# WS2812B-compact.net
KiCad netlist of a schematic drawn in EAGLE
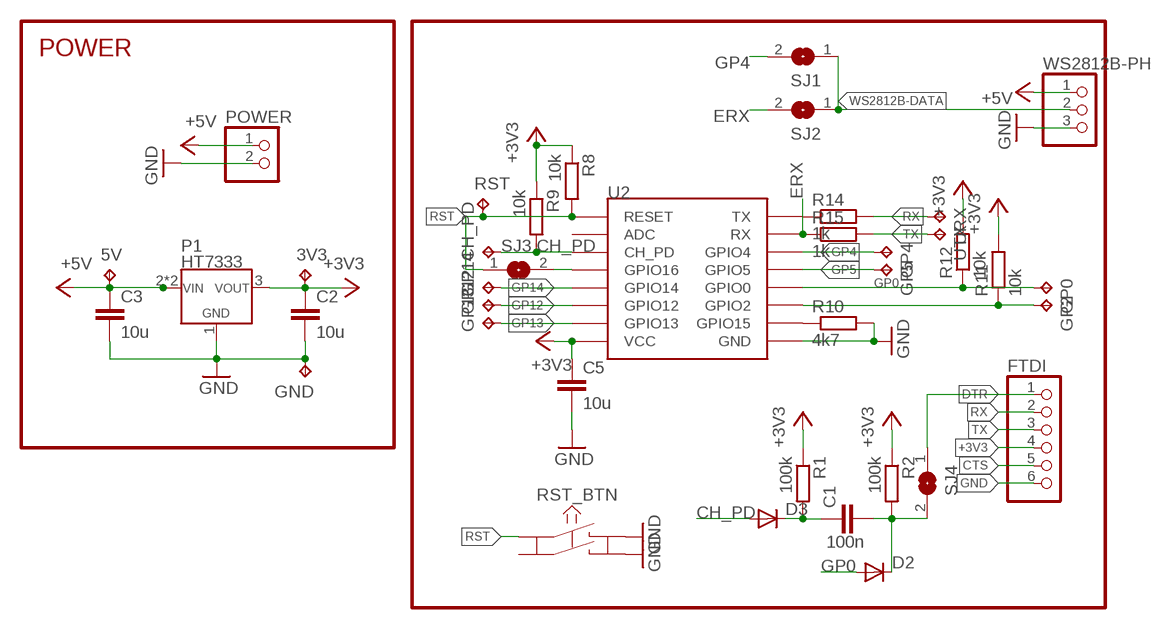
[diagram p0: schematic, sheet 1]

(export (version "E")
  (design (tool "Eeschema 10.0.6"))
  (components
    (comp (ref "3V3")
      (value "TPB2,54")
      (footprint "eagle-import:B2,54")
      (libsource (lib "eagle-import") (part "TPB2,54"))
    )
    (comp (ref "5V")
      (value "TPB2,54")
      (footprint "eagle-import:B2,54")
      (libsource (lib "eagle-import") (part "TPB2,54"))
    )
    (comp (ref "C1")
      (value "100n")
      (footprint "eagle-import:C1206")
      (libsource (lib "eagle-import") (part "C-EUC1206"))
    )
    (comp (ref "C2")
      (value "10u")
      (footprint "eagle-import:C1206")
      (libsource (lib "eagle-import") (part "C-EUC1206"))
    )
    (comp (ref "C3")
      (value "10u")
      (footprint "eagle-import:C1206")
      (libsource (lib "eagle-import") (part "C-EUC1206"))
    )
    (comp (ref "C5")
      (value "10u")
      (footprint "eagle-import:C1206")
      (libsource (lib "eagle-import") (part "C-EUC1206"))
    )
    (comp (ref "CH_PD")
      (value "TPB1,27")
      (footprint "eagle-import:B1,27")
      (libsource (lib "eagle-import") (part "TPB1,27"))
    )
    (comp (ref "D2")
      (value "DIODE-MINIMELF")
      (footprint "eagle-import:MINIMELF")
      (libsource (lib "eagle-import") (part "DIODE-MINIMELF"))
    )
    (comp (ref "D3")
      (value "DIODE-MINIMELF")
      (footprint "eagle-import:MINIMELF")
      (libsource (lib "eagle-import") (part "DIODE-MINIMELF"))
    )
    (comp (ref "FTDI")
      (value "PINHD-1X06_2.54-S")
      (footprint "eagle-import:1X06-S")
      (libsource (lib "eagle-import") (part "PINHD-1X06_2.54-S"))
    )
    (comp (ref "GND")
      (value "TPB2,54")
      (footprint "eagle-import:B2,54")
      (libsource (lib "eagle-import") (part "TPB2,54"))
    )
    (comp (ref "GP0")
      (value "TPB1,27")
      (footprint "eagle-import:B1,27")
      (libsource (lib "eagle-import") (part "TPB1,27"))
    )
    (comp (ref "GP2")
      (value "TPB1,27")
      (footprint "eagle-import:B1,27")
      (libsource (lib "eagle-import") (part "TPB1,27"))
    )
    (comp (ref "GP4")
      (value "TPB1,27")
      (footprint "eagle-import:B1,27")
      (libsource (lib "eagle-import") (part "TPB1,27"))
    )
    (comp (ref "GP5")
      (value "TPB1,27")
      (footprint "eagle-import:B1,27")
      (libsource (lib "eagle-import") (part "TPB1,27"))
    )
    (comp (ref "GP12")
      (value "TPB1,27")
      (footprint "eagle-import:B1,27")
      (libsource (lib "eagle-import") (part "TPB1,27"))
    )
    (comp (ref "GP13")
      (value "TPB1,27")
      (footprint "eagle-import:B1,27")
      (libsource (lib "eagle-import") (part "TPB1,27"))
    )
    (comp (ref "GP14")
      (value "TPB1,27")
      (footprint "eagle-import:B1,27")
      (libsource (lib "eagle-import") (part "TPB1,27"))
    )
    (comp (ref "P1")
      (value "HT7333")
      (footprint "eagle-import:SOT223")
      (libsource (lib "eagle-import") (part "HT7333"))
    )
    (comp (ref "POWER")
      (value "PINHD-1X2")
      (footprint "eagle-import:1X02")
      (libsource (lib "eagle-import") (part "PINHD-1X2"))
    )
    (comp (ref "R1")
      (value "100k")
      (footprint "eagle-import:R0805")
      (libsource (lib "eagle-import") (part "R-EU_R0805"))
    )
    (comp (ref "R2")
      (value "100k")
      (footprint "eagle-import:R0805")
      (libsource (lib "eagle-import") (part "R-EU_R0805"))
    )
    (comp (ref "R8")
      (value "10k")
      (footprint "eagle-import:R0805")
      (libsource (lib "eagle-import") (part "R-EU_R0805"))
    )
    (comp (ref "R9")
      (value "10k")
      (footprint "eagle-import:R0805")
      (libsource (lib "eagle-import") (part "R-EU_R0805"))
    )
    (comp (ref "R10")
      (value "4k7")
      (footprint "eagle-import:R0805")
      (libsource (lib "eagle-import") (part "R-EU_R0805"))
    )
    (comp (ref "R11")
      (value "10k")
      (footprint "eagle-import:R0805")
      (libsource (lib "eagle-import") (part "R-EU_R0805"))
    )
    (comp (ref "R12")
      (value "10k")
      (footprint "eagle-import:R0805")
      (libsource (lib "eagle-import") (part "R-EU_R0805"))
    )
    (comp (ref "R14")
      (value "1k")
      (footprint "eagle-import:R0805")
      (libsource (lib "eagle-import") (part "R-EU_R0805"))
    )
    (comp (ref "R15")
      (value "1k")
      (footprint "eagle-import:R0805")
      (libsource (lib "eagle-import") (part "R-EU_R0805"))
    )
    (comp (ref "RST")
      (value "TPB1,27")
      (footprint "eagle-import:B1,27")
      (libsource (lib "eagle-import") (part "TPB1,27"))
    )
    (comp (ref "RST_BTN")
      (value "KSM611A")
      (footprint "eagle-import:KSM611A")
      (libsource (lib "eagle-import") (part "KSM611A"))
    )
    (comp (ref "SJ1") (value "SJ") (footprint "eagle-import:SJ") (libsource (lib "eagle-import") (part "SJ")))
    (comp (ref "SJ2") (value "SJ") (footprint "eagle-import:SJ") (libsource (lib "eagle-import") (part "SJ")))
    (comp (ref "SJ3") (value "SJ") (footprint "eagle-import:SJ") (libsource (lib "eagle-import") (part "SJ")))
    (comp (ref "SJ4") (value "SJ") (footprint "eagle-import:SJ") (libsource (lib "eagle-import") (part "SJ")))
    (comp (ref "U2")
      (value "ESP12SMD")
      (footprint "eagle-import:ESP12-SMD")
      (libsource (lib "eagle-import") (part "ESP12SMD"))
    )
    (comp (ref "URX")
      (value "TPB1,27")
      (footprint "eagle-import:B1,27")
      (libsource (lib "eagle-import") (part "TPB1,27"))
    )
    (comp (ref "UTX")
      (value "TPB1,27")
      (footprint "eagle-import:B1,27")
      (libsource (lib "eagle-import") (part "TPB1,27"))
    )
    (comp (ref "WS2812B-PH")
      (value "PINHD-1X03_2.54-S")
      (footprint "eagle-import:1X03-S")
      (libsource (lib "eagle-import") (part "PINHD-1X03_2.54-S"))
    )
  )
  (nets
    (net (code "1") (name "+3V3") (class "Default")
      (node (ref "3V3") (pin "TP") (pinfunction "TP_TP") (pintype "input"))
      (node (ref "C2") (pin "1") (pinfunction "1_1") (pintype "passive"))
      (node (ref "C5") (pin "1") (pinfunction "1_1") (pintype "passive"))
      (node (ref "FTDI") (pin "4") (pinfunction "4_4") (pintype "passive"))
      (node (ref "P1") (pin "3") (pinfunction "VOUT_3") (pintype "power_in"))
      (node (ref "R1") (pin "1") (pinfunction "1_1") (pintype "passive"))
      (node (ref "R11") (pin "2") (pinfunction "2_2") (pintype "passive"))
      (node (ref "R12") (pin "2") (pinfunction "2_2") (pintype "passive"))
      (node (ref "R2") (pin "1") (pinfunction "1_1") (pintype "passive"))
      (node (ref "R8") (pin "1") (pinfunction "1_1") (pintype "passive"))
      (node (ref "R9") (pin "1") (pinfunction "1_1") (pintype "passive"))
      (node (ref "U2") (pin "VCC") (pinfunction "VCC_VCC") (pintype "bidirectional"))
    )
    (net (code "2") (name "+5V") (class "Default")
      (node (ref "5V") (pin "TP") (pinfunction "TP_TP") (pintype "input"))
      (node (ref "C3") (pin "1") (pinfunction "1_1") (pintype "passive"))
      (node (ref "P1") (pin "2") (pinfunction "VIN_2") (pintype "power_in"))
      (node (ref "P1") (pin "4") (pinfunction "VIN_4") (pintype "power_in"))
      (node (ref "POWER") (pin "1") (pinfunction "1_1") (pintype "passive"))
      (node (ref "WS2812B-PH") (pin "1") (pinfunction "1_1") (pintype "passive"))
    )
    (net (code "3") (name "/CH_PD") (class "Default")
      (node (ref "CH_PD") (pin "TP") (pinfunction "TP_TP") (pintype "input"))
      (node (ref "D3") (pin "A") (pinfunction "A_A") (pintype "passive"))
      (node (ref "R9") (pin "2") (pinfunction "2_2") (pintype "passive"))
      (node (ref "U2") (pin "CH_PD") (pinfunction "CH_PD_CH_PD") (pintype "bidirectional"))
    )
    (net (code "4") (name "/ERX") (class "Default")
      (node (ref "R15") (pin "1") (pinfunction "1_1") (pintype "passive"))
      (node (ref "SJ2") (pin "2") (pinfunction "2_2") (pintype "passive"))
      (node (ref "U2") (pin "RXD0") (pinfunction "RX_RXD0") (pintype "bidirectional"))
    )
    (net (code "5") (name "/GP0") (class "Default")
      (node (ref "D2") (pin "A") (pinfunction "A_A") (pintype "passive"))
      (node (ref "GP0") (pin "TP") (pinfunction "TP_TP") (pintype "input"))
      (node (ref "R12") (pin "1") (pinfunction "1_1") (pintype "passive"))
      (node (ref "U2") (pin "GPIO0") (pinfunction "GPIO0_GPIO0") (pintype "bidirectional"))
    )
    (net (code "6") (name "CTS") (class "Default")
      (node (ref "FTDI") (pin "5") (pinfunction "5_5") (pintype "passive"))
    )
    (net (code "7") (name "DTR") (class "Default")
      (node (ref "FTDI") (pin "1") (pinfunction "1_1") (pintype "passive"))
      (node (ref "SJ4") (pin "1") (pinfunction "1_1") (pintype "passive"))
    )
    (net (code "8") (name "GND") (class "Default")
      (node (ref "C2") (pin "2") (pinfunction "2_2") (pintype "passive"))
      (node (ref "C3") (pin "2") (pinfunction "2_2") (pintype "passive"))
      (node (ref "C5") (pin "2") (pinfunction "2_2") (pintype "passive"))
      (node (ref "FTDI") (pin "6") (pinfunction "6_6") (pintype "passive"))
      (node (ref "GND") (pin "TP") (pinfunction "TP_TP") (pintype "input"))
      (node (ref "P1") (pin "1") (pinfunction "GND_1") (pintype "power_in"))
      (node (ref "POWER") (pin "2") (pinfunction "2_2") (pintype "passive"))
      (node (ref "R10") (pin "2") (pinfunction "2_2") (pintype "passive"))
      (node (ref "RST_BTN") (pin "B") (pinfunction "B_B") (pintype "passive"))
      (node (ref "RST_BTN") (pin "D") (pinfunction "D_D") (pintype "passive"))
      (node (ref "U2") (pin "GND") (pinfunction "GND_GND") (pintype "bidirectional"))
      (node (ref "WS2812B-PH") (pin "3") (pinfunction "3_3") (pintype "passive"))
    )
    (net (code "9") (name "GP4") (class "Default")
      (node (ref "GP4") (pin "TP") (pinfunction "TP_TP") (pintype "input"))
      (node (ref "SJ1") (pin "2") (pinfunction "2_2") (pintype "passive"))
      (node (ref "U2") (pin "GPIO4") (pinfunction "GPIO4_GPIO4") (pintype "bidirectional"))
    )
    (net (code "10") (name "GP5") (class "Default")
      (node (ref "GP5") (pin "TP") (pinfunction "TP_TP") (pintype "input"))
      (node (ref "U2") (pin "GPIO5") (pinfunction "GPIO5_GPIO5") (pintype "bidirectional"))
    )
    (net (code "11") (name "GP12") (class "Default")
      (node (ref "GP12") (pin "TP") (pinfunction "TP_TP") (pintype "input"))
      (node (ref "U2") (pin "GPIO12") (pinfunction "GPIO12_GPIO12") (pintype "bidirectional"))
    )
    (net (code "12") (name "GP13") (class "Default")
      (node (ref "GP13") (pin "TP") (pinfunction "TP_TP") (pintype "input"))
      (node (ref "U2") (pin "GPIO13") (pinfunction "GPIO13_GPIO13") (pintype "bidirectional"))
    )
    (net (code "13") (name "GP14") (class "Default")
      (node (ref "GP14") (pin "TP") (pinfunction "TP_TP") (pintype "input"))
      (node (ref "U2") (pin "GPIO14") (pinfunction "GPIO14_GPIO14") (pintype "bidirectional"))
    )
    (net (code "14") (name "Net-(C1-Pad1)") (class "Default")
      (node (ref "C1") (pin "1") (pinfunction "1_1") (pintype "passive"))
      (node (ref "D3") (pin "C") (pinfunction "C_C") (pintype "passive"))
      (node (ref "R1") (pin "2") (pinfunction "2_2") (pintype "passive"))
    )
    (net (code "15") (name "Net-(C1-Pad2)") (class "Default")
      (node (ref "C1") (pin "2") (pinfunction "2_2") (pintype "passive"))
      (node (ref "D2") (pin "C") (pinfunction "C_C") (pintype "passive"))
      (node (ref "R2") (pin "2") (pinfunction "2_2") (pintype "passive"))
      (node (ref "SJ4") (pin "2") (pinfunction "2_2") (pintype "passive"))
    )
    (net (code "16") (name "Net-(GP2-PadTP)") (class "Default")
      (node (ref "GP2") (pin "TP") (pinfunction "TP_TP") (pintype "input"))
      (node (ref "R11") (pin "1") (pinfunction "1_1") (pintype "passive"))
      (node (ref "U2") (pin "GPIO2") (pinfunction "GPIO2_GPIO2") (pintype "bidirectional"))
    )
    (net (code "17") (name "Net-(R10-Pad1)") (class "Default")
      (node (ref "R10") (pin "1") (pinfunction "1_1") (pintype "passive"))
      (node (ref "U2") (pin "GPIO15") (pinfunction "GPIO15_GPIO15") (pintype "bidirectional"))
    )
    (net (code "18") (name "Net-(SJ3-Pad2)") (class "Default")
      (node (ref "SJ3") (pin "2") (pinfunction "2_2") (pintype "passive"))
      (node (ref "U2") (pin "GPIO16") (pinfunction "GPIO16_GPIO16") (pintype "bidirectional"))
    )
    (net (code "19") (name "Net-(U2-TX)") (class "Default")
      (node (ref "R14") (pin "1") (pinfunction "1_1") (pintype "passive"))
      (node (ref "U2") (pin "TXD0") (pinfunction "TX_TXD0") (pintype "bidirectional"))
    )
    (net (code "20") (name "RST") (class "Default")
      (node (ref "R8") (pin "2") (pinfunction "2_2") (pintype "passive"))
      (node (ref "RST") (pin "TP") (pinfunction "TP_TP") (pintype "input"))
      (node (ref "RST_BTN") (pin "A") (pinfunction "A_A") (pintype "passive"))
      (node (ref "SJ3") (pin "1") (pinfunction "1_1") (pintype "passive"))
      (node (ref "U2") (pin "RESET") (pinfunction "RESET_RESET") (pintype "bidirectional"))
    )
    (net (code "21") (name "RX") (class "Default")
      (node (ref "FTDI") (pin "2") (pinfunction "2_2") (pintype "passive"))
      (node (ref "R14") (pin "2") (pinfunction "2_2") (pintype "passive"))
      (node (ref "URX") (pin "TP") (pinfunction "TP_TP") (pintype "input"))
    )
    (net (code "22") (name "TX") (class "Default")
      (node (ref "FTDI") (pin "3") (pinfunction "3_3") (pintype "passive"))
      (node (ref "R15") (pin "2") (pinfunction "2_2") (pintype "passive"))
      (node (ref "UTX") (pin "TP") (pinfunction "TP_TP") (pintype "input"))
    )
    (net (code "23") (name "WS2812B-DATA") (class "Default")
      (node (ref "SJ1") (pin "1") (pinfunction "1_1") (pintype "passive"))
      (node (ref "SJ2") (pin "1") (pinfunction "1_1") (pintype "passive"))
      (node (ref "WS2812B-PH") (pin "2") (pinfunction "2_2") (pintype "passive"))
    )
    (net (code "24") (name "unconnected-(RST_BTN-PadC)") (class "Default")
      (node (ref "RST_BTN") (pin "C") (pinfunction "C_C") (pintype "passive"))
    )
    (net (code "25") (name "unconnected-(U2-PadADC)") (class "Default")
      (node (ref "U2") (pin "ADC") (pinfunction "ADC_ADC") (pintype "bidirectional"))
    )
  )
)
